# Tiva_board.net
KiCad netlist of a schematic drawn in EAGLE
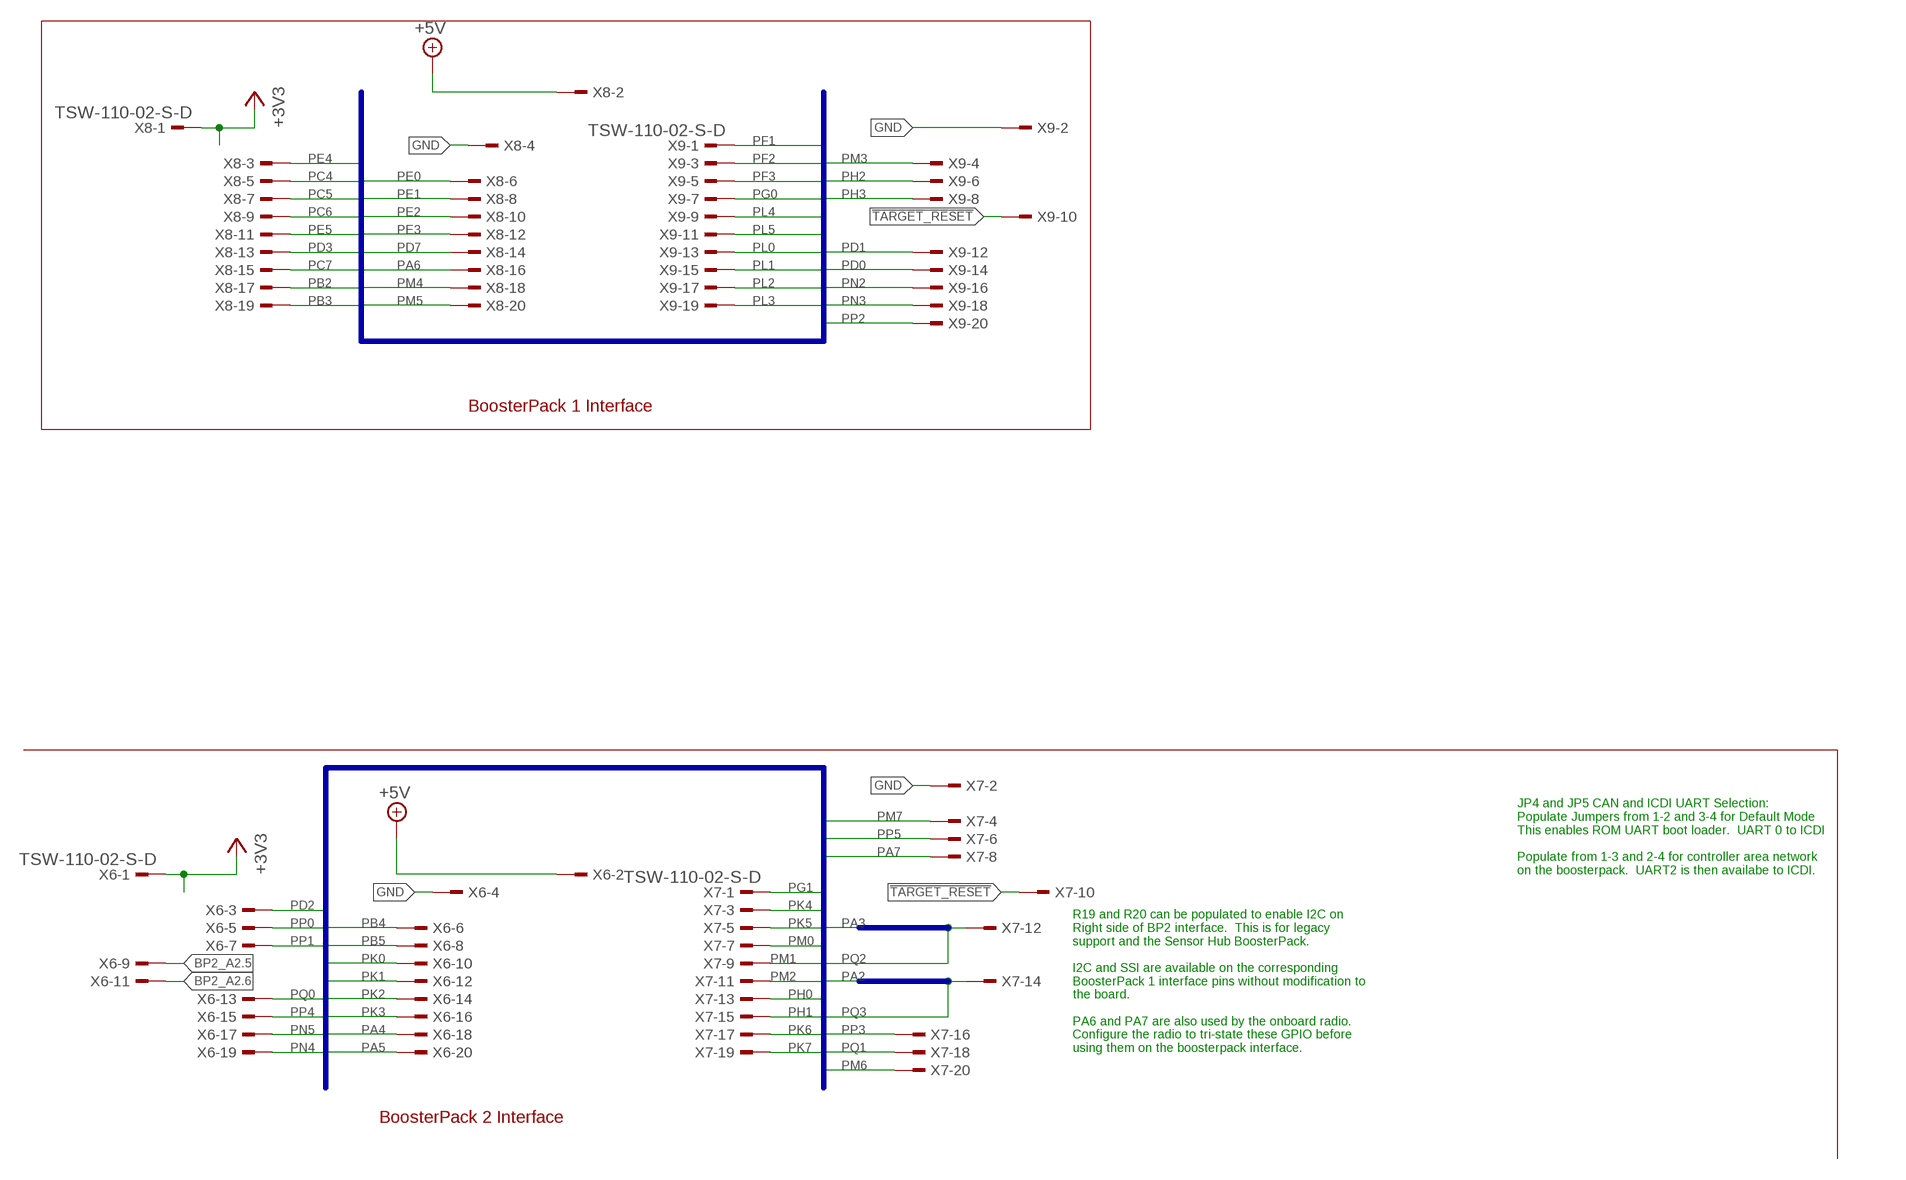
[diagram p0: schematic, sheet 1]

(export (version "E")
  (design (tool "Eeschema 10.0.6"))
  (components
    (comp (ref "X6")
      (value "TSW-110-02-S-D")
      (footprint "eagle-import:TSW-110-02-S-D")
      (fields (field (name "GNUM") "G22-THSTK-2X10-BAC"))
      (libsource (lib "eagle-import") (part "TSW-110-02-S-D"))
    )
    (comp (ref "X7")
      (value "TSW-110-02-S-D")
      (footprint "eagle-import:TSW-110-02-S-D")
      (fields (field (name "GNUM") "G22-THSTK-2X10-BAC"))
      (libsource (lib "eagle-import") (part "TSW-110-02-S-D"))
    )
    (comp (ref "X8")
      (value "TSW-110-02-S-D")
      (footprint "eagle-import:TSW-110-02-S-D")
      (fields (field (name "GNUM") "G22-THSTK-2X10-BAC"))
      (libsource (lib "eagle-import") (part "TSW-110-02-S-D"))
    )
    (comp (ref "X9")
      (value "TSW-110-02-S-D")
      (footprint "eagle-import:TSW-110-02-S-D")
      (fields (field (name "GNUM") "G22-THSTK-2X10-BAC"))
      (libsource (lib "eagle-import") (part "TSW-110-02-S-D"))
    )
  )
  (nets
    (net (code "1") (name "+3V3") (class "Default")
      (node (ref "X6") (pin "1") (pinfunction "1_1") (pintype "passive"))
      (node (ref "X8") (pin "1") (pinfunction "1_1") (pintype "passive"))
    )
    (net (code "2") (name "+5V") (class "Default")
      (node (ref "X6") (pin "2") (pinfunction "1_2") (pintype "passive"))
      (node (ref "X8") (pin "2") (pinfunction "1_2") (pintype "passive"))
    )
    (net (code "5") (name "/PA4") (class "Default")
      (node (ref "X6") (pin "18") (pinfunction "1_18") (pintype "passive"))
    )
    (net (code "6") (name "/PA5") (class "Default")
      (node (ref "X6") (pin "20") (pinfunction "1_20") (pintype "passive"))
    )
    (net (code "7") (name "/PA6") (class "Default")
      (node (ref "X8") (pin "16") (pinfunction "1_16") (pintype "passive"))
    )
    (net (code "8") (name "/PA7") (class "Default")
      (node (ref "X7") (pin "8") (pinfunction "1_8") (pintype "passive"))
    )
    (net (code "9") (name "/PB2") (class "Default")
      (node (ref "X8") (pin "17") (pinfunction "1_17") (pintype "passive"))
    )
    (net (code "10") (name "/PB3") (class "Default")
      (node (ref "X8") (pin "19") (pinfunction "1_19") (pintype "passive"))
    )
    (net (code "11") (name "/PB4") (class "Default")
      (node (ref "X6") (pin "6") (pinfunction "1_6") (pintype "passive"))
    )
    (net (code "12") (name "/PB5") (class "Default")
      (node (ref "X6") (pin "8") (pinfunction "1_8") (pintype "passive"))
    )
    (net (code "13") (name "/PC4") (class "Default")
      (node (ref "X8") (pin "5") (pinfunction "1_5") (pintype "passive"))
    )
    (net (code "14") (name "/PC5") (class "Default")
      (node (ref "X8") (pin "7") (pinfunction "1_7") (pintype "passive"))
    )
    (net (code "15") (name "/PC6") (class "Default")
      (node (ref "X8") (pin "9") (pinfunction "1_9") (pintype "passive"))
    )
    (net (code "16") (name "/PC7") (class "Default")
      (node (ref "X8") (pin "15") (pinfunction "1_15") (pintype "passive"))
    )
    (net (code "17") (name "/PD0") (class "Default")
      (node (ref "X9") (pin "14") (pinfunction "1_14") (pintype "passive"))
    )
    (net (code "18") (name "/PD1") (class "Default")
      (node (ref "X9") (pin "12") (pinfunction "1_12") (pintype "passive"))
    )
    (net (code "19") (name "/PD2") (class "Default")
      (node (ref "X6") (pin "3") (pinfunction "1_3") (pintype "passive"))
    )
    (net (code "20") (name "/PD3") (class "Default")
      (node (ref "X8") (pin "13") (pinfunction "1_13") (pintype "passive"))
    )
    (net (code "21") (name "/PD7") (class "Default")
      (node (ref "X8") (pin "14") (pinfunction "1_14") (pintype "passive"))
    )
    (net (code "22") (name "/PE0") (class "Default")
      (node (ref "X8") (pin "6") (pinfunction "1_6") (pintype "passive"))
    )
    (net (code "23") (name "/PE1") (class "Default")
      (node (ref "X8") (pin "8") (pinfunction "1_8") (pintype "passive"))
    )
    (net (code "24") (name "/PE2") (class "Default")
      (node (ref "X8") (pin "10") (pinfunction "1_10") (pintype "passive"))
    )
    (net (code "25") (name "/PE3") (class "Default")
      (node (ref "X8") (pin "12") (pinfunction "1_12") (pintype "passive"))
    )
    (net (code "26") (name "/PE4") (class "Default")
      (node (ref "X8") (pin "3") (pinfunction "1_3") (pintype "passive"))
    )
    (net (code "27") (name "/PE5") (class "Default")
      (node (ref "X8") (pin "11") (pinfunction "1_11") (pintype "passive"))
    )
    (net (code "28") (name "/PF1") (class "Default")
      (node (ref "X9") (pin "1") (pinfunction "1_1") (pintype "passive"))
    )
    (net (code "29") (name "/PF2") (class "Default")
      (node (ref "X9") (pin "3") (pinfunction "1_3") (pintype "passive"))
    )
    (net (code "30") (name "/PF3") (class "Default")
      (node (ref "X9") (pin "5") (pinfunction "1_5") (pintype "passive"))
    )
    (net (code "31") (name "/PG0") (class "Default")
      (node (ref "X9") (pin "7") (pinfunction "1_7") (pintype "passive"))
    )
    (net (code "32") (name "/PG1") (class "Default")
      (node (ref "X7") (pin "1") (pinfunction "1_1") (pintype "passive"))
    )
    (net (code "33") (name "/PH0") (class "Default")
      (node (ref "X7") (pin "13") (pinfunction "1_13") (pintype "passive"))
    )
    (net (code "34") (name "/PH1") (class "Default")
      (node (ref "X7") (pin "15") (pinfunction "1_15") (pintype "passive"))
    )
    (net (code "35") (name "/PH2") (class "Default")
      (node (ref "X9") (pin "6") (pinfunction "1_6") (pintype "passive"))
    )
    (net (code "36") (name "/PH3") (class "Default")
      (node (ref "X9") (pin "8") (pinfunction "1_8") (pintype "passive"))
    )
    (net (code "37") (name "/PK0") (class "Default")
      (node (ref "X6") (pin "10") (pinfunction "1_10") (pintype "passive"))
    )
    (net (code "38") (name "/PK1") (class "Default")
      (node (ref "X6") (pin "12") (pinfunction "1_12") (pintype "passive"))
    )
    (net (code "39") (name "/PK2") (class "Default")
      (node (ref "X6") (pin "14") (pinfunction "1_14") (pintype "passive"))
    )
    (net (code "40") (name "/PK3") (class "Default")
      (node (ref "X6") (pin "16") (pinfunction "1_16") (pintype "passive"))
    )
    (net (code "41") (name "/PK4") (class "Default")
      (node (ref "X7") (pin "3") (pinfunction "1_3") (pintype "passive"))
    )
    (net (code "42") (name "/PK5") (class "Default")
      (node (ref "X7") (pin "5") (pinfunction "1_5") (pintype "passive"))
    )
    (net (code "43") (name "/PK6") (class "Default")
      (node (ref "X7") (pin "17") (pinfunction "1_17") (pintype "passive"))
    )
    (net (code "44") (name "/PK7") (class "Default")
      (node (ref "X7") (pin "19") (pinfunction "1_19") (pintype "passive"))
    )
    (net (code "45") (name "/PL0") (class "Default")
      (node (ref "X9") (pin "13") (pinfunction "1_13") (pintype "passive"))
    )
    (net (code "46") (name "/PL1") (class "Default")
      (node (ref "X9") (pin "15") (pinfunction "1_15") (pintype "passive"))
    )
    (net (code "47") (name "/PL2") (class "Default")
      (node (ref "X9") (pin "17") (pinfunction "1_17") (pintype "passive"))
    )
    (net (code "48") (name "/PL3") (class "Default")
      (node (ref "X9") (pin "19") (pinfunction "1_19") (pintype "passive"))
    )
    (net (code "49") (name "/PL4") (class "Default")
      (node (ref "X9") (pin "9") (pinfunction "1_9") (pintype "passive"))
    )
    (net (code "50") (name "/PL5") (class "Default")
      (node (ref "X9") (pin "11") (pinfunction "1_11") (pintype "passive"))
    )
    (net (code "51") (name "/PM0") (class "Default")
      (node (ref "X7") (pin "7") (pinfunction "1_7") (pintype "passive"))
    )
    (net (code "52") (name "/PM1") (class "Default")
      (node (ref "X7") (pin "9") (pinfunction "1_9") (pintype "passive"))
    )
    (net (code "53") (name "/PM2") (class "Default")
      (node (ref "X7") (pin "11") (pinfunction "1_11") (pintype "passive"))
    )
    (net (code "54") (name "/PM3") (class "Default")
      (node (ref "X9") (pin "4") (pinfunction "1_4") (pintype "passive"))
    )
    (net (code "55") (name "/PM4") (class "Default")
      (node (ref "X8") (pin "18") (pinfunction "1_18") (pintype "passive"))
    )
    (net (code "56") (name "/PM5") (class "Default")
      (node (ref "X8") (pin "20") (pinfunction "1_20") (pintype "passive"))
    )
    (net (code "57") (name "/PM6") (class "Default")
      (node (ref "X7") (pin "20") (pinfunction "1_20") (pintype "passive"))
    )
    (net (code "58") (name "/PM7") (class "Default")
      (node (ref "X7") (pin "4") (pinfunction "1_4") (pintype "passive"))
    )
    (net (code "59") (name "/PN2") (class "Default")
      (node (ref "X9") (pin "16") (pinfunction "1_16") (pintype "passive"))
    )
    (net (code "60") (name "/PN3") (class "Default")
      (node (ref "X9") (pin "18") (pinfunction "1_18") (pintype "passive"))
    )
    (net (code "61") (name "/PN4") (class "Default")
      (node (ref "X6") (pin "19") (pinfunction "1_19") (pintype "passive"))
    )
    (net (code "62") (name "/PN5") (class "Default")
      (node (ref "X6") (pin "17") (pinfunction "1_17") (pintype "passive"))
    )
    (net (code "63") (name "/PP0") (class "Default")
      (node (ref "X6") (pin "5") (pinfunction "1_5") (pintype "passive"))
    )
    (net (code "64") (name "/PP1") (class "Default")
      (node (ref "X6") (pin "7") (pinfunction "1_7") (pintype "passive"))
    )
    (net (code "65") (name "/PP2") (class "Default")
      (node (ref "X9") (pin "20") (pinfunction "1_20") (pintype "passive"))
    )
    (net (code "66") (name "/PP3") (class "Default")
      (node (ref "X7") (pin "16") (pinfunction "1_16") (pintype "passive"))
    )
    (net (code "67") (name "/PP4") (class "Default")
      (node (ref "X6") (pin "15") (pinfunction "1_15") (pintype "passive"))
    )
    (net (code "68") (name "/PP5") (class "Default")
      (node (ref "X7") (pin "6") (pinfunction "1_6") (pintype "passive"))
    )
    (net (code "69") (name "/PQ0") (class "Default")
      (node (ref "X6") (pin "13") (pinfunction "1_13") (pintype "passive"))
    )
    (net (code "70") (name "/PQ1") (class "Default")
      (node (ref "X7") (pin "18") (pinfunction "1_18") (pintype "passive"))
    )
    (net (code "71") (name "/PQ2") (class "Default")
      (node (ref "X7") (pin "12") (pinfunction "1_12") (pintype "passive"))
    )
    (net (code "72") (name "/PQ3") (class "Default")
      (node (ref "X7") (pin "14") (pinfunction "1_14") (pintype "passive"))
    )
    (net (code "73") (name "/~{TARGET_RESET}") (class "Default")
      (node (ref "X7") (pin "10") (pinfunction "1_10") (pintype "passive"))
      (node (ref "X9") (pin "10") (pinfunction "1_10") (pintype "passive"))
    )
    (net (code "74") (name "BP2_A2.5") (class "Default")
      (node (ref "X6") (pin "9") (pinfunction "1_9") (pintype "passive"))
    )
    (net (code "75") (name "BP2_A2.6") (class "Default")
      (node (ref "X6") (pin "11") (pinfunction "1_11") (pintype "passive"))
    )
    (net (code "76") (name "GND") (class "Default")
      (node (ref "X6") (pin "4") (pinfunction "1_4") (pintype "passive"))
      (node (ref "X7") (pin "2") (pinfunction "1_2") (pintype "passive"))
      (node (ref "X8") (pin "4") (pinfunction "1_4") (pintype "passive"))
      (node (ref "X9") (pin "2") (pinfunction "1_2") (pintype "passive"))
    )
  )
)
